# BBB_Connections.net
KiCad netlist of a schematic drawn in Altium Designer
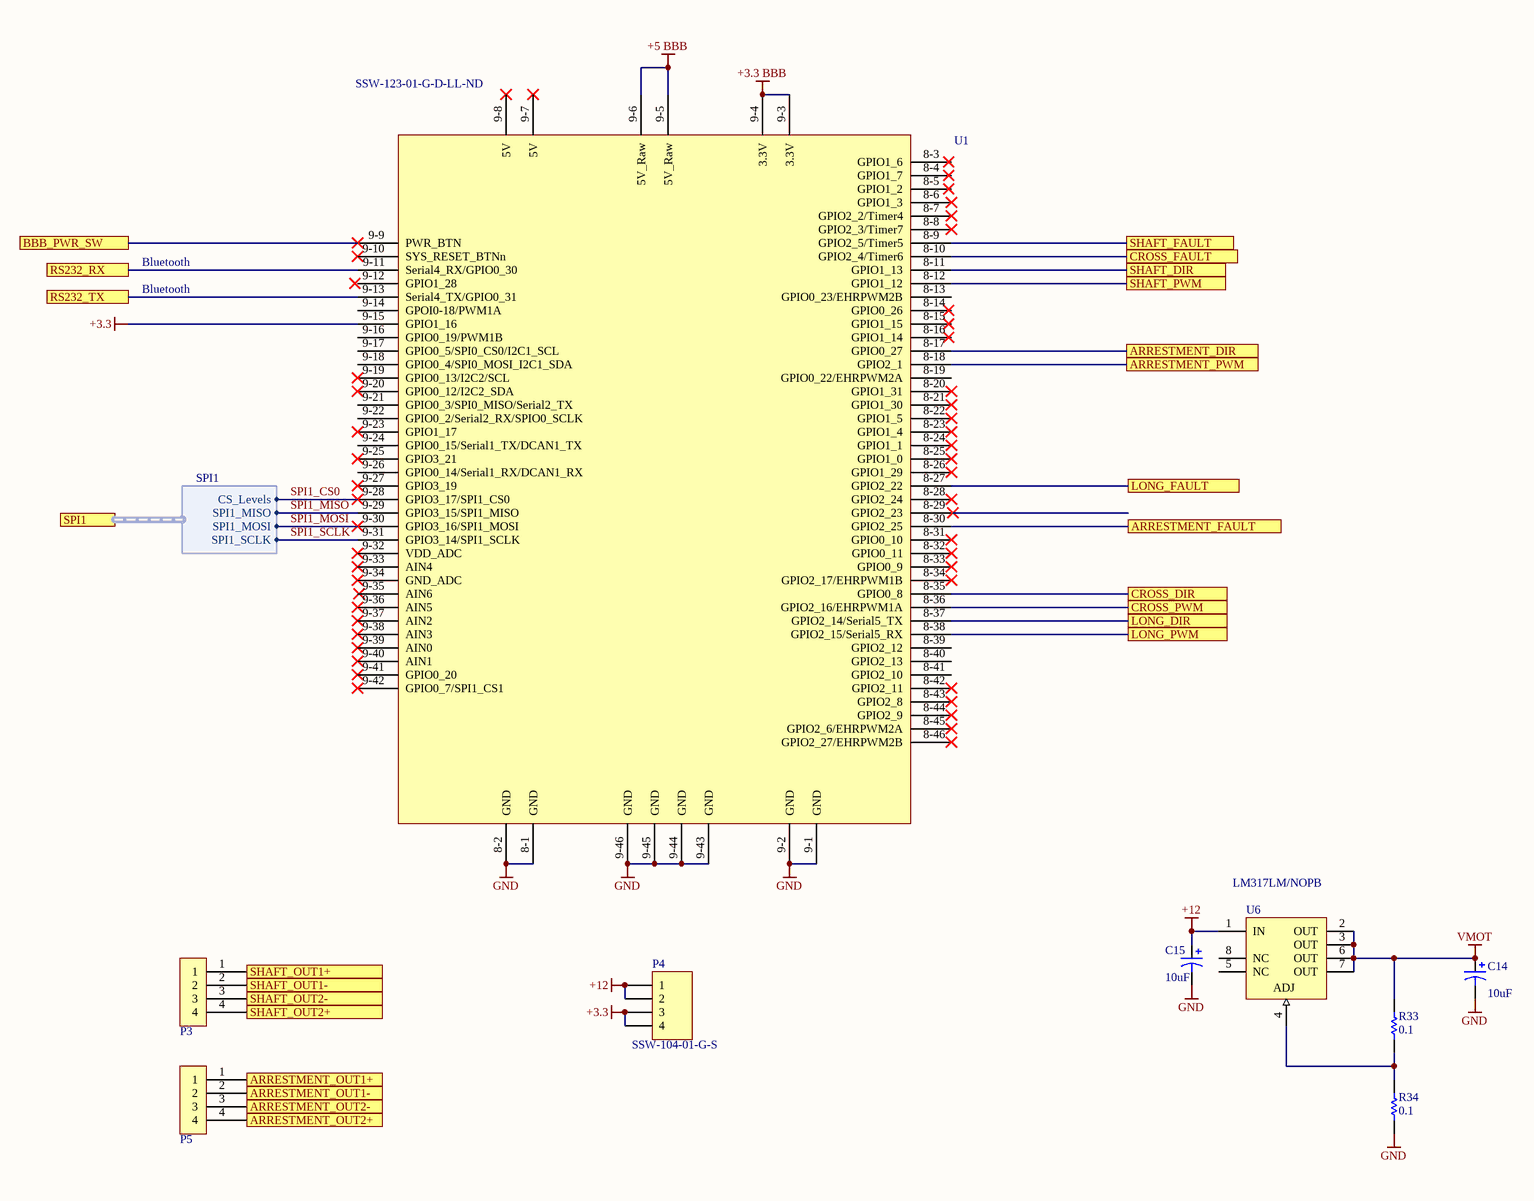
[diagram p0: BBB_Connections.SchDoc]

(export (version "E")
  (design (tool "Eeschema 10.0.6"))
  (components
    (comp (ref "C14")
      (value "10uF")
      (footprint "C0805")
      (description "Polarized Capacitor (Surface Mount)")
      (fields (field (name "Comment") "Cap Pol3") (field (name "PUBLISHER") "Altium Limited"))
      (libsource (lib "Miscellaneous Devices") (part "Cap Pol3"))
    )
    (comp (ref "C15")
      (value "10uF")
      (footprint "C0805")
      (description "Polarized Capacitor (Surface Mount)")
      (fields (field (name "Comment") "Cap Pol3") (field (name "PUBLISHER") "Altium Limited"))
      (libsource (lib "Miscellaneous Devices") (part "Cap Pol3"))
    )
    (comp (ref "P3")
      (value "IPL1-104-01-F-S-RA")
      (footprint "IPL1-104-01-L-S-RA-K")
      (libsource (lib "ZLS_Schematic_lib") (part "IPL1-104-01-F-S-RA"))
    )
    (comp (ref "P4")
      (value "SSW-104-01-G-S")
      (footprint "HDR1X4")
      (description "Header, 4-Pin")
      (fields (field (name "MANUFACTURER") "Samtec Inc."))
      (libsource (lib "Miscellaneous Connectors") (part "Header 4"))
    )
    (comp (ref "P5")
      (value "IPL1-104-01-F-S-RA")
      (footprint "IPL1-104-01-L-S-RA-K")
      (libsource (lib "ZLS_Schematic_lib") (part "IPL1-104-01-F-S-RA"))
    )
    (comp (ref "R33")
      (value "0.1")
      (footprint "RESC0805(2012)_L")
      (description "RES SMD 1R OHM 1% 1/8W 0805")
      (fields
        (field (name "MANUFACTURER") "Vishay Dale")
        (field (name "MANUFACTURER PART NUMBER") "CRCW080510K0FKEA")
      )
      (libsource (lib "Altium Content Vault") (part "CMP-1013-00215-1"))
    )
    (comp (ref "R34")
      (value "0.1")
      (footprint "RESC0805(2012)_L")
      (description "RES SMD 1R OHM 1% 1/8W 0805")
      (fields
        (field (name "MANUFACTURER") "Vishay Dale")
        (field (name "MANUFACTURER PART NUMBER") "CRCW080510K0FKEA")
      )
      (libsource (lib "Altium Content Vault") (part "CMP-1013-00215-1"))
    )
    (comp (ref "U1")
      (value "BBB")
      (footprint "Beaglebone Black Mezanine")
      (description "Beaglebone Black")
      (fields
        (field (name "SUPPLIER PART NUMBER 1") "SSW-123-01-G-D-LL-ND")
        (field (name "MANUFACTURER") "Samtec Inc.")
        (field (name "MANUFACTURER PART NUMBER") "SSW-123-01-G-D-LL")
      )
      (libsource (lib "ZLS_Schematic_lib") (part "Beaglebone_Black_Mezanine"))
    )
    (comp (ref "U6")
      (value "LM317LM/NOPB")
      (footprint "M08A_M")
      (description "3-Terminal Adjustable Regulator, 8-pin Narrow SOIC, Pb-Free")
      (fields (field (name "MANUFACTURER") "National Semiconductor"))
      (libsource (lib "Altium Content Vault") (part "PM-REG-LM317-IL8"))
    )
  )
  (nets
    (net (code "2") (name "+3.3") (class "Default")
      (node (ref "P4") (pin "3") (pinfunction "3_3") (pintype "passive"))
      (node (ref "P4") (pin "4") (pinfunction "4_4") (pintype "passive"))
      (node (ref "U1") (pin "9-15") (pinfunction "GPIO1_16_9-15") (pintype "passive"))
    )
    (net (code "3") (name "+3.3 BBB") (class "Default")
      (node (ref "U1") (pin "9-3") (pinfunction "3.3V_9-3") (pintype "passive"))
      (node (ref "U1") (pin "9-4") (pinfunction "3.3V_9-4") (pintype "passive"))
    )
    (net (code "4") (name "+5 BBB") (class "Default")
      (node (ref "U1") (pin "9-5") (pinfunction "5V_Raw_9-5") (pintype "passive"))
      (node (ref "U1") (pin "9-6") (pinfunction "5V_Raw_9-6") (pintype "passive"))
    )
    (net (code "5") (name "+12") (class "Default")
      (node (ref "C15") (pin "1") (pinfunction "1_1") (pintype "passive"))
      (node (ref "P4") (pin "1") (pinfunction "1_1") (pintype "passive"))
      (node (ref "P4") (pin "2") (pinfunction "2_2") (pintype "passive"))
      (node (ref "U6") (pin "1") (pinfunction "IN_1") (pintype "power_in"))
    )
    (net (code "6") (name "/ARRESTMENT_DIR") (class "Default")
      (node (ref "U1") (pin "8-17") (pinfunction "GPIO0_27_8-17") (pintype "passive"))
    )
    (net (code "7") (name "/ARRESTMENT_FAULT") (class "Default")
      (node (ref "U1") (pin "8-30") (pinfunction "GPIO2_25_8-30") (pintype "passive"))
    )
    (net (code "8") (name "/ARRESTMENT_OUT1+") (class "Default")
      (node (ref "P5") (pin "1") (pinfunction "1_1") (pintype "passive"))
    )
    (net (code "9") (name "/ARRESTMENT_OUT1-") (class "Default")
      (node (ref "P5") (pin "2") (pinfunction "2_2") (pintype "passive"))
    )
    (net (code "10") (name "/ARRESTMENT_OUT2+") (class "Default")
      (node (ref "P5") (pin "4") (pinfunction "4_4") (pintype "passive"))
    )
    (net (code "11") (name "/ARRESTMENT_OUT2-") (class "Default")
      (node (ref "P5") (pin "3") (pinfunction "3_3") (pintype "passive"))
    )
    (net (code "12") (name "/ARRESTMENT_PWM") (class "Default")
      (node (ref "U1") (pin "8-18") (pinfunction "GPIO2_1_8-18") (pintype "passive"))
    )
    (net (code "13") (name "/BBB_PWR_SW") (class "Default")
      (node (ref "U1") (pin "9-9") (pinfunction "PWR_BTN_9-9") (pintype "passive+no_connect"))
    )
    (net (code "14") (name "/CROSS_DIR") (class "Default")
      (node (ref "U1") (pin "8-35") (pinfunction "GPIO0_8_8-35") (pintype "passive"))
    )
    (net (code "15") (name "/CROSS_FAULT") (class "Default")
      (node (ref "U1") (pin "8-10") (pinfunction "GPIO2_4/Timer6_8-10") (pintype "passive"))
    )
    (net (code "16") (name "/CROSS_PWM") (class "Default")
      (node (ref "U1") (pin "8-36") (pinfunction "GPIO2_16/EHRPWM1A_8-36") (pintype "passive"))
    )
    (net (code "17") (name "/LONG_DIR") (class "Default")
      (node (ref "U1") (pin "8-37") (pinfunction "GPIO2_14/Serial5_TX_8-37") (pintype "passive"))
    )
    (net (code "18") (name "/LONG_FAULT") (class "Default")
      (node (ref "U1") (pin "8-27") (pinfunction "GPIO2_22_8-27") (pintype "passive"))
    )
    (net (code "19") (name "/LONG_PWM") (class "Default")
      (node (ref "U1") (pin "8-38") (pinfunction "GPIO2_15/Serial5_RX_8-38") (pintype "passive"))
    )
    (net (code "20") (name "/RS232_RX") (class "Default")
      (node (ref "U1") (pin "9-11") (pinfunction "Serial4_RX/GPIO0_30_9-11") (pintype "passive"))
    )
    (net (code "21") (name "/RS232_TX") (class "Default")
      (node (ref "U1") (pin "9-13") (pinfunction "Serial4_TX/GPIO0_31_9-13") (pintype "passive"))
    )
    (net (code "22") (name "/SHAFT_DIR") (class "Default")
      (node (ref "U1") (pin "8-11") (pinfunction "GPIO1_13_8-11") (pintype "passive"))
    )
    (net (code "23") (name "/SHAFT_FAULT") (class "Default")
      (node (ref "U1") (pin "8-9") (pinfunction "GPIO2_5/Timer5_8-9") (pintype "passive"))
    )
    (net (code "24") (name "/SHAFT_OUT1+") (class "Default")
      (node (ref "P3") (pin "1") (pinfunction "1_1") (pintype "passive"))
    )
    (net (code "25") (name "/SHAFT_OUT1-") (class "Default")
      (node (ref "P3") (pin "2") (pinfunction "2_2") (pintype "passive"))
    )
    (net (code "26") (name "/SHAFT_OUT2+") (class "Default")
      (node (ref "P3") (pin "4") (pinfunction "4_4") (pintype "passive"))
    )
    (net (code "27") (name "/SHAFT_OUT2-") (class "Default")
      (node (ref "P3") (pin "3") (pinfunction "3_3") (pintype "passive"))
    )
    (net (code "28") (name "/SHAFT_PWM") (class "Default")
      (node (ref "U1") (pin "8-12") (pinfunction "GPIO1_12_8-12") (pintype "passive"))
    )
    (net (code "29") (name "/SPI1_CS0") (class "Default")
      (node (ref "U1") (pin "9-28") (pinfunction "GPIO3_17/SPI1_CS0_9-28") (pintype "passive+no_connect"))
    )
    (net (code "30") (name "/SPI1_MISO") (class "Default")
      (node (ref "U1") (pin "9-29") (pinfunction "GPIO3_15/SPI1_MISO_9-29") (pintype "passive"))
    )
    (net (code "31") (name "/SPI1_MOSI") (class "Default")
      (node (ref "U1") (pin "9-30") (pinfunction "GPIO3_16/SPI1_MOSI_9-30") (pintype "passive+no_connect"))
    )
    (net (code "32") (name "/SPI1_SCLK") (class "Default")
      (node (ref "U1") (pin "9-31") (pinfunction "GPIO3_14/SPI1_SCLK_9-31") (pintype "passive"))
    )
    (net (code "34") (name "GND") (class "Default")
      (node (ref "C14") (pin "2") (pinfunction "2_2") (pintype "passive"))
      (node (ref "C15") (pin "2") (pinfunction "2_2") (pintype "passive"))
      (node (ref "R34") (pin "1") (pinfunction "1_1") (pintype "passive"))
      (node (ref "U1") (pin "8-1") (pinfunction "GND_8-1") (pintype "passive"))
      (node (ref "U1") (pin "8-2") (pinfunction "GND_8-2") (pintype "passive"))
      (node (ref "U1") (pin "9-1") (pinfunction "GND_9-1") (pintype "passive"))
      (node (ref "U1") (pin "9-2") (pinfunction "GND_9-2") (pintype "passive"))
      (node (ref "U1") (pin "9-43") (pinfunction "GND_9-43") (pintype "passive"))
      (node (ref "U1") (pin "9-44") (pinfunction "GND_9-44") (pintype "passive"))
      (node (ref "U1") (pin "9-45") (pinfunction "GND_9-45") (pintype "passive"))
      (node (ref "U1") (pin "9-46") (pinfunction "GND_9-46") (pintype "passive"))
    )
    (net (code "35") (name "Net-(U6-ADJ)") (class "Default")
      (node (ref "R33") (pin "1") (pinfunction "1_1") (pintype "passive"))
      (node (ref "R34") (pin "2") (pinfunction "2_2") (pintype "passive"))
      (node (ref "U6") (pin "4") (pinfunction "ADJ_4") (pintype "input"))
    )
    (net (code "36") (name "VMOT") (class "Default")
      (node (ref "C14") (pin "1") (pinfunction "1_1") (pintype "passive"))
      (node (ref "R33") (pin "2") (pinfunction "2_2") (pintype "passive"))
      (node (ref "U6") (pin "2") (pinfunction "OUT_2") (pintype "power_in"))
      (node (ref "U6") (pin "3") (pinfunction "OUT_3") (pintype "power_in"))
      (node (ref "U6") (pin "6") (pinfunction "OUT_6") (pintype "power_in"))
      (node (ref "U6") (pin "7") (pinfunction "OUT_7") (pintype "power_in"))
    )
    (net (code "37") (name "unconnected-(U1-5V-Pad9-7)") (class "Default")
      (node (ref "U1") (pin "9-7") (pinfunction "5V_9-7") (pintype "passive+no_connect"))
    )
    (net (code "38") (name "unconnected-(U1-5V-Pad9-8)") (class "Default")
      (node (ref "U1") (pin "9-8") (pinfunction "5V_9-8") (pintype "passive+no_connect"))
    )
    (net (code "39") (name "unconnected-(U1-AIN0-Pad9-39)") (class "Default")
      (node (ref "U1") (pin "9-39") (pinfunction "AIN0_9-39") (pintype "passive+no_connect"))
    )
    (net (code "40") (name "unconnected-(U1-AIN1-Pad9-40)") (class "Default")
      (node (ref "U1") (pin "9-40") (pinfunction "AIN1_9-40") (pintype "passive+no_connect"))
    )
    (net (code "41") (name "unconnected-(U1-AIN2-Pad9-37)") (class "Default")
      (node (ref "U1") (pin "9-37") (pinfunction "AIN2_9-37") (pintype "passive+no_connect"))
    )
    (net (code "42") (name "unconnected-(U1-AIN3-Pad9-38)") (class "Default")
      (node (ref "U1") (pin "9-38") (pinfunction "AIN3_9-38") (pintype "passive+no_connect"))
    )
    (net (code "43") (name "unconnected-(U1-AIN4-Pad9-33)") (class "Default")
      (node (ref "U1") (pin "9-33") (pinfunction "AIN4_9-33") (pintype "passive+no_connect"))
    )
    (net (code "44") (name "unconnected-(U1-AIN5-Pad9-36)") (class "Default")
      (node (ref "U1") (pin "9-36") (pinfunction "AIN5_9-36") (pintype "passive+no_connect"))
    )
    (net (code "45") (name "unconnected-(U1-AIN6-Pad9-35)") (class "Default")
      (node (ref "U1") (pin "9-35") (pinfunction "AIN6_9-35") (pintype "passive"))
    )
    (net (code "46") (name "unconnected-(U1-GND_ADC-Pad9-34)") (class "Default")
      (node (ref "U1") (pin "9-34") (pinfunction "GND_ADC_9-34") (pintype "passive+no_connect"))
    )
    (net (code "47") (name "unconnected-(U1-GPIO0_2{slash}Serial2_RX{slash}SPIO0_SCLK-Pad9-22)") (class "Default")
      (node (ref "U1") (pin "9-22") (pinfunction "GPIO0_2/Serial2_RX/SPIO0_SCLK_9-22") (pintype "passive"))
    )
    (net (code "48") (name "unconnected-(U1-GPIO0_3{slash}SPI0_MISO{slash}Serial2_TX-Pad9-21)") (class "Default")
      (node (ref "U1") (pin "9-21") (pinfunction "GPIO0_3/SPI0_MISO/Serial2_TX_9-21") (pintype "passive"))
    )
    (net (code "49") (name "unconnected-(U1-GPIO0_4{slash}SPI0_MOSI_I2C1_SDA-Pad9-18)") (class "Default")
      (node (ref "U1") (pin "9-18") (pinfunction "GPIO0_4/SPI0_MOSI_I2C1_SDA_9-18") (pintype "passive"))
    )
    (net (code "50") (name "unconnected-(U1-GPIO0_5{slash}SPI0_CS0{slash}I2C1_SCL-Pad9-17)") (class "Default")
      (node (ref "U1") (pin "9-17") (pinfunction "GPIO0_5/SPI0_CS0/I2C1_SCL_9-17") (pintype "passive"))
    )
    (net (code "51") (name "unconnected-(U1-GPIO0_7{slash}SPI1_CS1-Pad9-42)") (class "Default")
      (node (ref "U1") (pin "9-42") (pinfunction "GPIO0_7/SPI1_CS1_9-42") (pintype "passive+no_connect"))
    )
    (net (code "52") (name "unconnected-(U1-GPIO0_9-Pad8-33)") (class "Default")
      (node (ref "U1") (pin "8-33") (pinfunction "GPIO0_9_8-33") (pintype "passive+no_connect"))
    )
    (net (code "53") (name "unconnected-(U1-GPIO0_10-Pad8-31)") (class "Default")
      (node (ref "U1") (pin "8-31") (pinfunction "GPIO0_10_8-31") (pintype "passive+no_connect"))
    )
    (net (code "54") (name "unconnected-(U1-GPIO0_11-Pad8-32)") (class "Default")
      (node (ref "U1") (pin "8-32") (pinfunction "GPIO0_11_8-32") (pintype "passive+no_connect"))
    )
    (net (code "55") (name "unconnected-(U1-GPIO0_12{slash}I2C2_SDA-Pad9-20)") (class "Default")
      (node (ref "U1") (pin "9-20") (pinfunction "GPIO0_12/I2C2_SDA_9-20") (pintype "passive+no_connect"))
    )
    (net (code "56") (name "unconnected-(U1-GPIO0_13{slash}I2C2{slash}SCL-Pad9-19)") (class "Default")
      (node (ref "U1") (pin "9-19") (pinfunction "GPIO0_13/I2C2/SCL_9-19") (pintype "passive+no_connect"))
    )
    (net (code "57") (name "unconnected-(U1-GPIO0_14{slash}Serial1_RX{slash}DCAN1_RX-Pad9-26)") (class "Default")
      (node (ref "U1") (pin "9-26") (pinfunction "GPIO0_14/Serial1_RX/DCAN1_RX_9-26") (pintype "passive"))
    )
    (net (code "58") (name "unconnected-(U1-GPIO0_15{slash}Serial1_TX{slash}DCAN1_TX-Pad9-24)") (class "Default")
      (node (ref "U1") (pin "9-24") (pinfunction "GPIO0_15/Serial1_TX/DCAN1_TX_9-24") (pintype "passive"))
    )
    (net (code "59") (name "unconnected-(U1-GPIO0_19{slash}PWM1B-Pad9-16)") (class "Default")
      (node (ref "U1") (pin "9-16") (pinfunction "GPIO0_19/PWM1B_9-16") (pintype "passive"))
    )
    (net (code "60") (name "unconnected-(U1-GPIO0_20-Pad9-41)") (class "Default")
      (node (ref "U1") (pin "9-41") (pinfunction "GPIO0_20_9-41") (pintype "passive+no_connect"))
    )
    (net (code "61") (name "unconnected-(U1-GPIO0_22{slash}EHRPWM2A-Pad8-19)") (class "Default")
      (node (ref "U1") (pin "8-19") (pinfunction "GPIO0_22/EHRPWM2A_8-19") (pintype "passive"))
    )
    (net (code "62") (name "unconnected-(U1-GPIO0_23{slash}EHRPWM2B-Pad8-13)") (class "Default")
      (node (ref "U1") (pin "8-13") (pinfunction "GPIO0_23/EHRPWM2B_8-13") (pintype "passive"))
    )
    (net (code "63") (name "unconnected-(U1-GPIO0_26-Pad8-14)") (class "Default")
      (node (ref "U1") (pin "8-14") (pinfunction "GPIO0_26_8-14") (pintype "passive"))
    )
    (net (code "64") (name "unconnected-(U1-GPIO1_0-Pad8-25)") (class "Default")
      (node (ref "U1") (pin "8-25") (pinfunction "GPIO1_0_8-25") (pintype "passive+no_connect"))
    )
    (net (code "65") (name "unconnected-(U1-GPIO1_1-Pad8-24)") (class "Default")
      (node (ref "U1") (pin "8-24") (pinfunction "GPIO1_1_8-24") (pintype "passive+no_connect"))
    )
    (net (code "66") (name "unconnected-(U1-GPIO1_2-Pad8-5)") (class "Default")
      (node (ref "U1") (pin "8-5") (pinfunction "GPIO1_2_8-5") (pintype "passive"))
    )
    (net (code "67") (name "unconnected-(U1-GPIO1_3-Pad8-6)") (class "Default")
      (node (ref "U1") (pin "8-6") (pinfunction "GPIO1_3_8-6") (pintype "passive+no_connect"))
    )
    (net (code "68") (name "unconnected-(U1-GPIO1_4-Pad8-23)") (class "Default")
      (node (ref "U1") (pin "8-23") (pinfunction "GPIO1_4_8-23") (pintype "passive+no_connect"))
    )
    (net (code "69") (name "unconnected-(U1-GPIO1_5-Pad8-22)") (class "Default")
      (node (ref "U1") (pin "8-22") (pinfunction "GPIO1_5_8-22") (pintype "passive+no_connect"))
    )
    (net (code "70") (name "unconnected-(U1-GPIO1_6-Pad8-3)") (class "Default")
      (node (ref "U1") (pin "8-3") (pinfunction "GPIO1_6_8-3") (pintype "passive"))
    )
    (net (code "71") (name "unconnected-(U1-GPIO1_7-Pad8-4)") (class "Default")
      (node (ref "U1") (pin "8-4") (pinfunction "GPIO1_7_8-4") (pintype "passive"))
    )
    (net (code "72") (name "unconnected-(U1-GPIO1_14-Pad8-16)") (class "Default")
      (node (ref "U1") (pin "8-16") (pinfunction "GPIO1_14_8-16") (pintype "passive"))
    )
    (net (code "73") (name "unconnected-(U1-GPIO1_15-Pad8-15)") (class "Default")
      (node (ref "U1") (pin "8-15") (pinfunction "GPIO1_15_8-15") (pintype "passive"))
    )
    (net (code "74") (name "unconnected-(U1-GPIO1_17-Pad9-23)") (class "Default")
      (node (ref "U1") (pin "9-23") (pinfunction "GPIO1_17_9-23") (pintype "passive+no_connect"))
    )
    (net (code "75") (name "unconnected-(U1-GPIO1_28-Pad9-12)") (class "Default")
      (node (ref "U1") (pin "9-12") (pinfunction "GPIO1_28_9-12") (pintype "passive"))
    )
    (net (code "76") (name "unconnected-(U1-GPIO1_29-Pad8-26)") (class "Default")
      (node (ref "U1") (pin "8-26") (pinfunction "GPIO1_29_8-26") (pintype "passive+no_connect"))
    )
    (net (code "77") (name "unconnected-(U1-GPIO1_30-Pad8-21)") (class "Default")
      (node (ref "U1") (pin "8-21") (pinfunction "GPIO1_30_8-21") (pintype "passive+no_connect"))
    )
    (net (code "78") (name "unconnected-(U1-GPIO1_31-Pad8-20)") (class "Default")
      (node (ref "U1") (pin "8-20") (pinfunction "GPIO1_31_8-20") (pintype "passive+no_connect"))
    )
    (net (code "79") (name "unconnected-(U1-GPIO2_2{slash}Timer4-Pad8-7)") (class "Default")
      (node (ref "U1") (pin "8-7") (pinfunction "GPIO2_2/Timer4_8-7") (pintype "passive+no_connect"))
    )
    (net (code "80") (name "unconnected-(U1-GPIO2_3{slash}Timer7-Pad8-8)") (class "Default")
      (node (ref "U1") (pin "8-8") (pinfunction "GPIO2_3/Timer7_8-8") (pintype "passive+no_connect"))
    )
    (net (code "81") (name "unconnected-(U1-GPIO2_6{slash}EHRPWM2A-Pad8-45)") (class "Default")
      (node (ref "U1") (pin "8-45") (pinfunction "GPIO2_6/EHRPWM2A_8-45") (pintype "passive+no_connect"))
    )
    (net (code "82") (name "unconnected-(U1-GPIO2_8-Pad8-43)") (class "Default")
      (node (ref "U1") (pin "8-43") (pinfunction "GPIO2_8_8-43") (pintype "passive+no_connect"))
    )
    (net (code "83") (name "unconnected-(U1-GPIO2_9-Pad8-44)") (class "Default")
      (node (ref "U1") (pin "8-44") (pinfunction "GPIO2_9_8-44") (pintype "passive+no_connect"))
    )
    (net (code "84") (name "unconnected-(U1-GPIO2_10-Pad8-41)") (class "Default")
      (node (ref "U1") (pin "8-41") (pinfunction "GPIO2_10_8-41") (pintype "passive"))
    )
    (net (code "85") (name "unconnected-(U1-GPIO2_11-Pad8-42)") (class "Default")
      (node (ref "U1") (pin "8-42") (pinfunction "GPIO2_11_8-42") (pintype "passive+no_connect"))
    )
    (net (code "86") (name "unconnected-(U1-GPIO2_12-Pad8-39)") (class "Default")
      (node (ref "U1") (pin "8-39") (pinfunction "GPIO2_12_8-39") (pintype "passive"))
    )
    (net (code "87") (name "unconnected-(U1-GPIO2_13-Pad8-40)") (class "Default")
      (node (ref "U1") (pin "8-40") (pinfunction "GPIO2_13_8-40") (pintype "passive"))
    )
    (net (code "88") (name "unconnected-(U1-GPIO2_17{slash}EHRPWM1B-Pad8-34)") (class "Default")
      (node (ref "U1") (pin "8-34") (pinfunction "GPIO2_17/EHRPWM1B_8-34") (pintype "passive+no_connect"))
    )
    (net (code "89") (name "unconnected-(U1-GPIO2_23-Pad8-29)") (class "Default")
      (node (ref "U1") (pin "8-29") (pinfunction "GPIO2_23_8-29") (pintype "passive"))
    )
    (net (code "90") (name "unconnected-(U1-GPIO2_24-Pad8-28)") (class "Default")
      (node (ref "U1") (pin "8-28") (pinfunction "GPIO2_24_8-28") (pintype "passive+no_connect"))
    )
    (net (code "91") (name "unconnected-(U1-GPIO2_27{slash}EHRPWM2B-Pad8-46)") (class "Default")
      (node (ref "U1") (pin "8-46") (pinfunction "GPIO2_27/EHRPWM2B_8-46") (pintype "passive+no_connect"))
    )
    (net (code "92") (name "unconnected-(U1-GPIO3_19-Pad9-27)") (class "Default")
      (node (ref "U1") (pin "9-27") (pinfunction "GPIO3_19_9-27") (pintype "passive+no_connect"))
    )
    (net (code "93") (name "unconnected-(U1-GPIO3_21-Pad9-25)") (class "Default")
      (node (ref "U1") (pin "9-25") (pinfunction "GPIO3_21_9-25") (pintype "passive+no_connect"))
    )
    (net (code "94") (name "unconnected-(U1-GPOI0-18{slash}PWM1A-Pad9-14)") (class "Default")
      (node (ref "U1") (pin "9-14") (pinfunction "GPOI0-18/PWM1A_9-14") (pintype "passive"))
    )
    (net (code "95") (name "unconnected-(U1-SYS_RESET_BTNn-Pad9-10)") (class "Default")
      (node (ref "U1") (pin "9-10") (pinfunction "SYS_RESET_BTNn_9-10") (pintype "passive+no_connect"))
    )
    (net (code "96") (name "unconnected-(U1-VDD_ADC-Pad9-32)") (class "Default")
      (node (ref "U1") (pin "9-32") (pinfunction "VDD_ADC_9-32") (pintype "passive+no_connect"))
    )
    (net (code "97") (name "unconnected-(U6-NC-Pad5)") (class "Default")
      (node (ref "U6") (pin "5") (pinfunction "NC_5") (pintype "passive"))
    )
    (net (code "98") (name "unconnected-(U6-NC-Pad8)") (class "Default")
      (node (ref "U6") (pin "8") (pinfunction "NC_8") (pintype "passive"))
    )
  )
)
